# tx_no_transistor.net
KiCad netlist of a schematic drawn in EAGLE
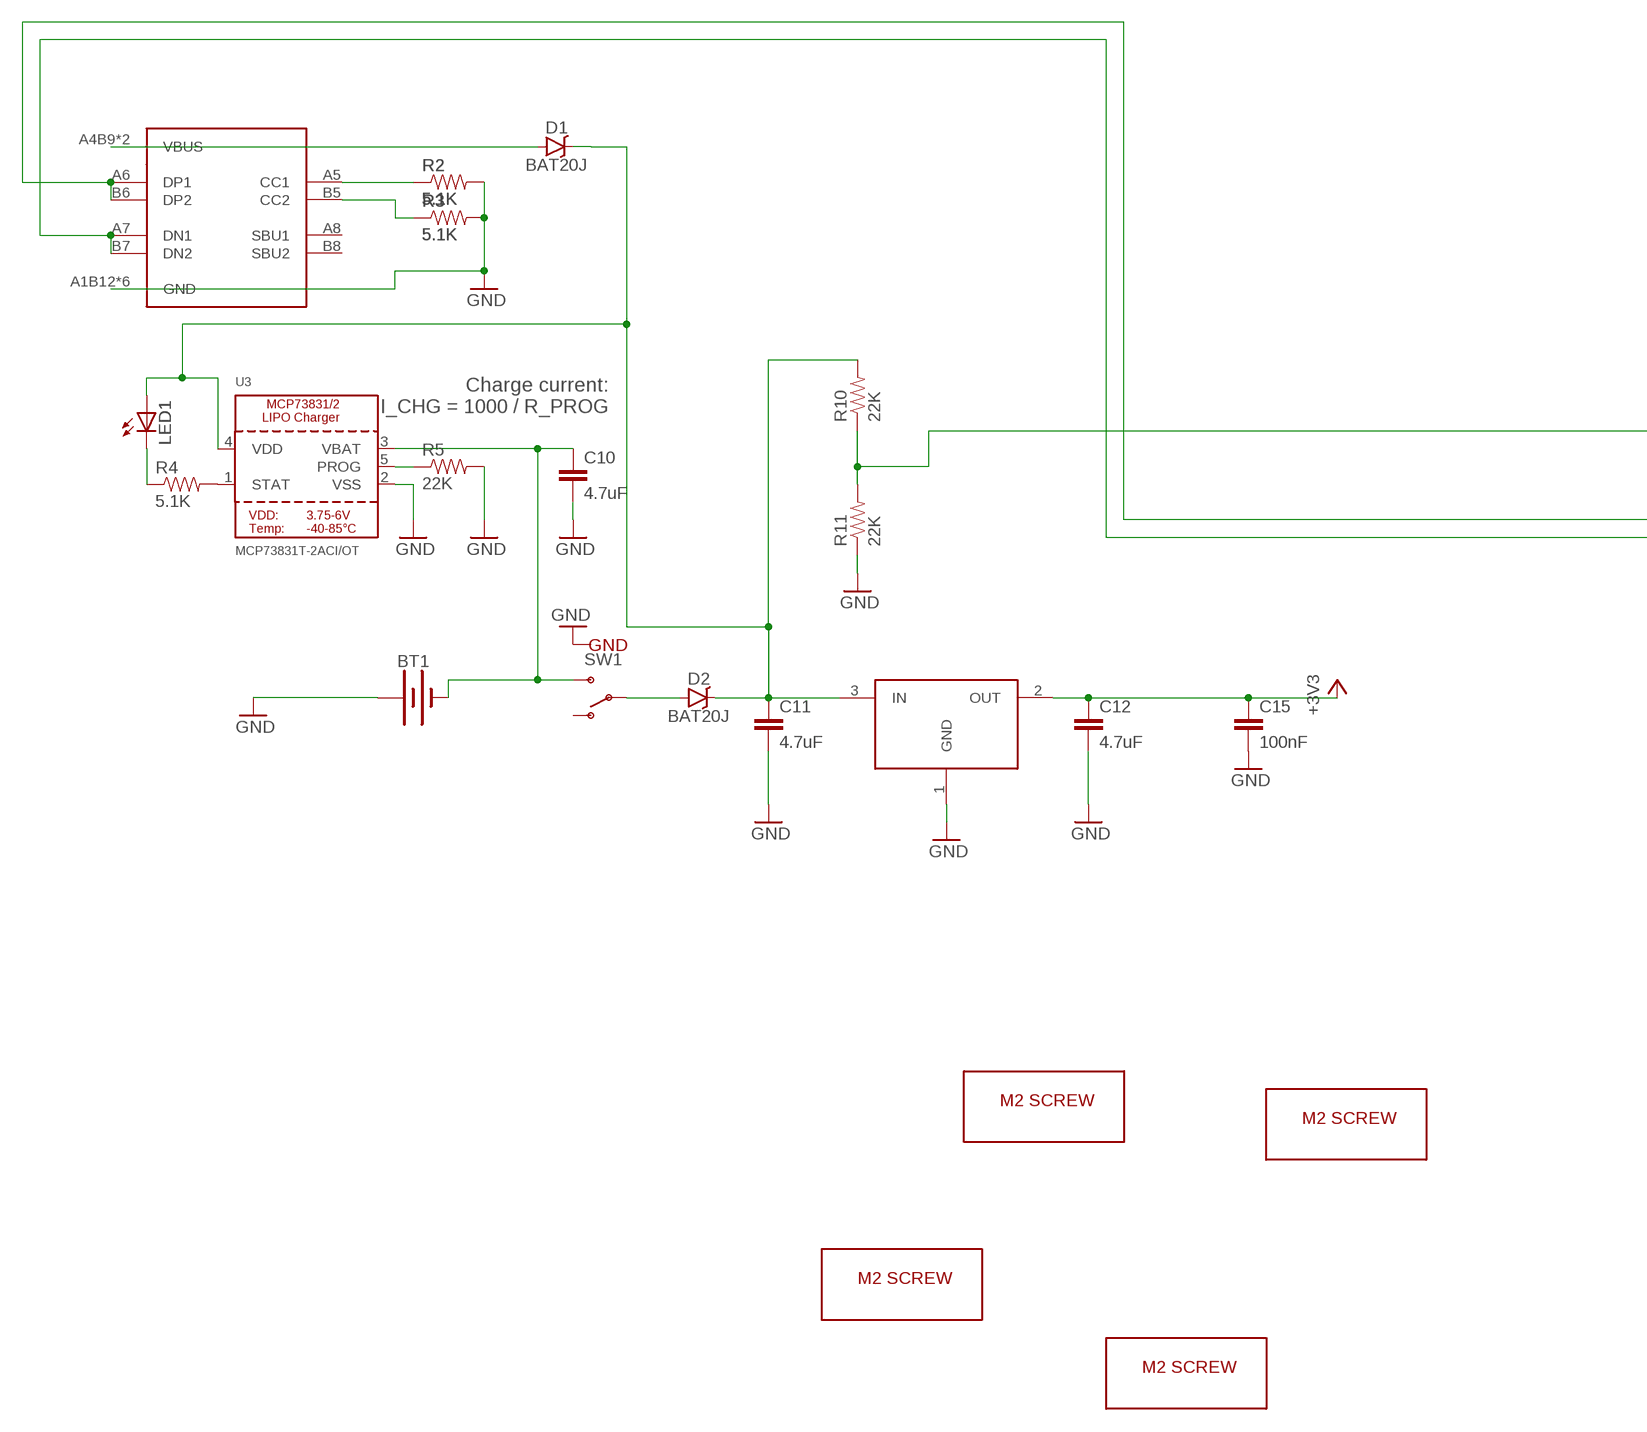
[diagram p0: schematic, sheet 1, part 1 of 2]
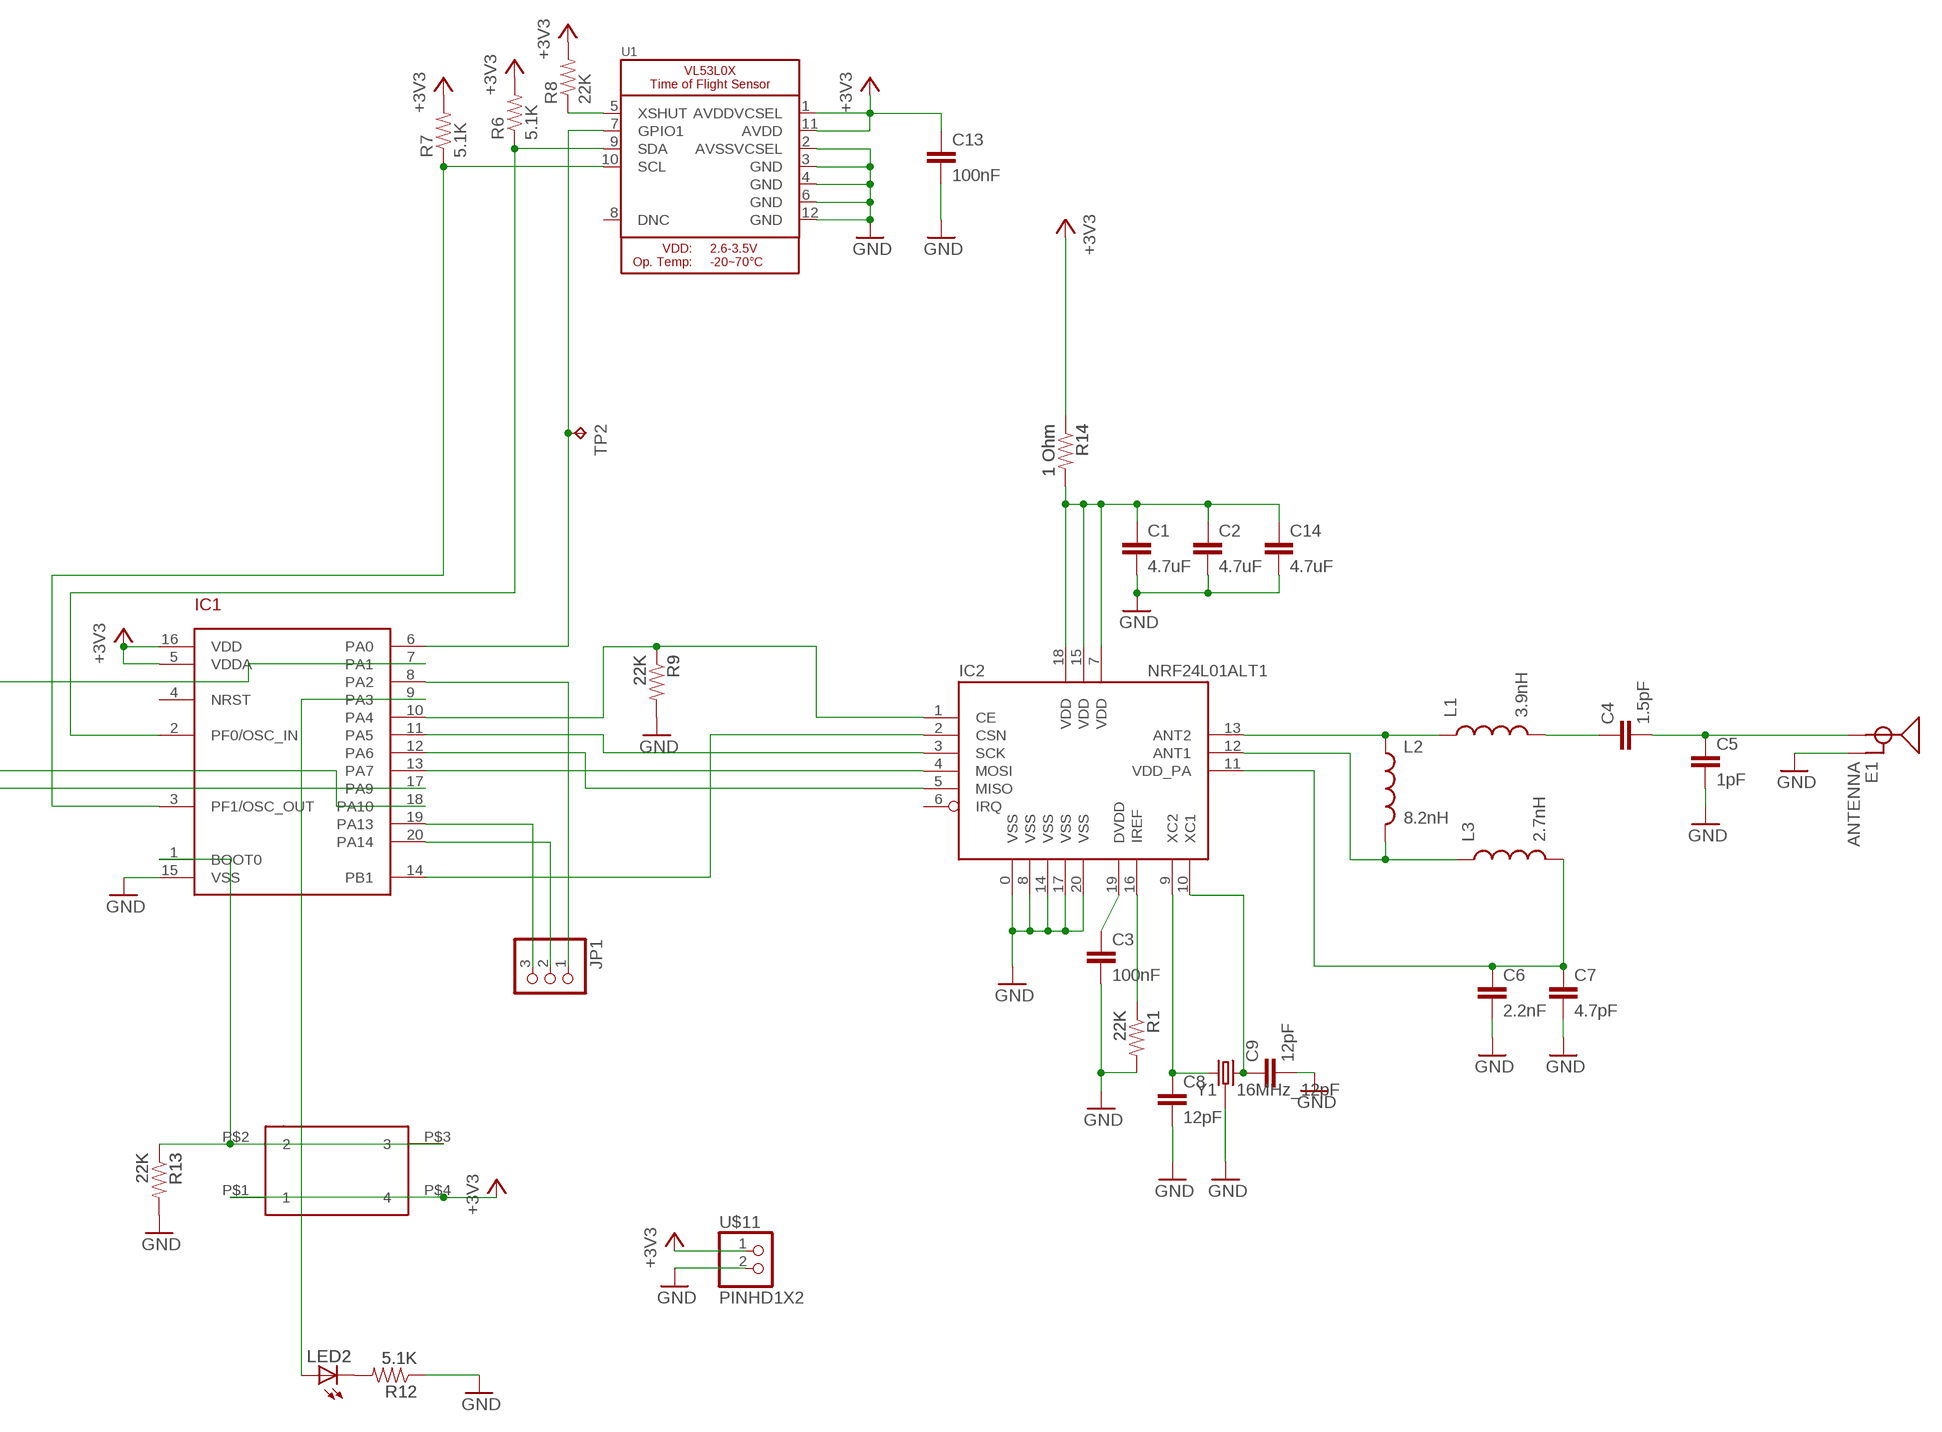
[diagram p1: schematic, sheet 1, part 2 of 2]

(export (version "E")
  (design (tool "Eeschema 10.0.6"))
  (components
    (comp (ref "BT1")
      (value "TX_SPARKFUN-BATTERIES_BATTERY-24.5MM_PTH")
      (footprint "eagle-import:TX_SPARKFUN-BATTERIES_BATTCON_24.5MM_PTH")
      (libsource (lib "eagle-import") (part "TX_SPARKFUN-BATTERIES_BATTERY-24.5MM_PTH"))
    )
    (comp (ref "C1")
      (value "4.7uF")
      (footprint "eagle-import:0805")
      (libsource (lib "eagle-import") (part "clock_CAP0805"))
    )
    (comp (ref "C2")
      (value "4.7uF")
      (footprint "eagle-import:0805")
      (libsource (lib "eagle-import") (part "clock_CAP0805"))
    )
    (comp (ref "C3")
      (value "100nF")
      (footprint "eagle-import:0805")
      (libsource (lib "eagle-import") (part "clock_CAP0805"))
    )
    (comp (ref "C4")
      (value "1.5pF")
      (footprint "eagle-import:0805")
      (libsource (lib "eagle-import") (part "clock_CAP0805"))
    )
    (comp (ref "C5")
      (value "1pF")
      (footprint "eagle-import:0805")
      (libsource (lib "eagle-import") (part "clock_CAP0805"))
    )
    (comp (ref "C6")
      (value "2.2nF")
      (footprint "eagle-import:0805")
      (libsource (lib "eagle-import") (part "clock_CAP0805"))
    )
    (comp (ref "C7")
      (value "4.7pF")
      (footprint "eagle-import:0805")
      (libsource (lib "eagle-import") (part "clock_CAP0805"))
    )
    (comp (ref "C8")
      (value "12pF")
      (footprint "eagle-import:0805")
      (libsource (lib "eagle-import") (part "clock_CAP0805"))
    )
    (comp (ref "C9")
      (value "12pF")
      (footprint "eagle-import:0805")
      (libsource (lib "eagle-import") (part "clock_CAP0805"))
    )
    (comp (ref "C10")
      (value "4.7uF")
      (footprint "eagle-import:0805")
      (libsource (lib "eagle-import") (part "CAP0805"))
    )
    (comp (ref "C11")
      (value "4.7uF")
      (footprint "eagle-import:0805")
      (libsource (lib "eagle-import") (part "clock_CAP0805"))
    )
    (comp (ref "C12")
      (value "4.7uF")
      (footprint "eagle-import:0805")
      (libsource (lib "eagle-import") (part "clock_CAP0805"))
    )
    (comp (ref "C13")
      (value "100nF")
      (footprint "eagle-import:0805")
      (libsource (lib "eagle-import") (part "clock_CAP0805"))
    )
    (comp (ref "C14")
      (value "4.7uF")
      (footprint "eagle-import:0805")
      (libsource (lib "eagle-import") (part "clock_CAP0805"))
    )
    (comp (ref "C15")
      (value "100nF")
      (footprint "eagle-import:0805")
      (libsource (lib "eagle-import") (part "clock_CAP0805"))
    )
    (comp (ref "D1")
      (value "BAT20J")
      (footprint "eagle-import:SOD-323")
      (libsource (lib "eagle-import") (part "DIODE-SCHOTTKY-BAT20J"))
    )
    (comp (ref "D2")
      (value "BAT20J")
      (footprint "eagle-import:SOD-323")
      (libsource (lib "eagle-import") (part "DIODE-SCHOTTKY-BAT20J"))
    )
    (comp (ref "E1")
      (value "ANTENNA")
      (footprint "eagle-import:TRACE_ANTENNA_2.4GHZ_25.7MM_TUNED")
      (libsource (lib "eagle-import") (part "ANTENNATRACE-TUNED"))
    )
    (comp (ref "IC1")
      (value "STM32F030F4")
      (footprint "eagle-import:TSSOP20")
      (libsource (lib "eagle-import") (part "STM32F030F4"))
    )
    (comp (ref "IC2")
      (value "NRF24L01ALT1")
      (footprint "eagle-import:QFN20_ALT1")
      (libsource (lib "eagle-import") (part "NRF24L01ALT1"))
    )
    (comp (ref "JP1")
      (value "PINHD-1X3CB")
      (footprint "eagle-import:1X03-CLEANBIG")
      (libsource (lib "eagle-import") (part "PINHD-1X3CB"))
    )
    (comp (ref "L1")
      (value "3.9nH")
      (footprint "eagle-import:0805")
      (libsource (lib "eagle-import") (part "INDUCTOR0805"))
    )
    (comp (ref "L2")
      (value "8.2nH")
      (footprint "eagle-import:0805")
      (libsource (lib "eagle-import") (part "INDUCTOR0805"))
    )
    (comp (ref "L3")
      (value "2.7nH")
      (footprint "eagle-import:0805")
      (libsource (lib "eagle-import") (part "INDUCTOR0805"))
    )
    (comp (ref "LED1")
      (value "LEDCHIP-LED0805")
      (footprint "eagle-import:CHIP-LED0805")
      (libsource (lib "eagle-import") (part "LEDCHIP-LED0805"))
    )
    (comp (ref "LED2")
      (value "LEDCHIP-LED0805")
      (footprint "eagle-import:CHIP-LED0805")
      (libsource (lib "eagle-import") (part "LEDCHIP-LED0805"))
    )
    (comp (ref "R1")
      (value "22K")
      (footprint "eagle-import:0805")
      (libsource (lib "eagle-import") (part "joyAnalog_RESISTOR0805-RES"))
    )
    (comp (ref "R2")
      (value "5.1K")
      (footprint "eagle-import:0805")
      (libsource (lib "eagle-import") (part "joyAnalog_RESISTOR0805-RES"))
    )
    (comp (ref "R3")
      (value "5.1K")
      (footprint "eagle-import:0805")
      (libsource (lib "eagle-import") (part "joyAnalog_RESISTOR0805-RES"))
    )
    (comp (ref "R4")
      (value "5.1K")
      (footprint "eagle-import:0805")
      (libsource (lib "eagle-import") (part "RESISTOR0805-RES"))
    )
    (comp (ref "R5")
      (value "22K")
      (footprint "eagle-import:0805")
      (libsource (lib "eagle-import") (part "RESISTOR0805-RES"))
    )
    (comp (ref "R6")
      (value "5.1K")
      (footprint "eagle-import:0805")
      (libsource (lib "eagle-import") (part "RESISTOR0805-RES"))
    )
    (comp (ref "R7")
      (value "5.1K")
      (footprint "eagle-import:0805")
      (libsource (lib "eagle-import") (part "RESISTOR0805-RES"))
    )
    (comp (ref "R8")
      (value "22K")
      (footprint "eagle-import:0805")
      (libsource (lib "eagle-import") (part "RESISTOR0805-RES"))
    )
    (comp (ref "R9")
      (value "22K")
      (footprint "eagle-import:0805")
      (libsource (lib "eagle-import") (part "joyAnalog_RESISTOR0805-RES"))
    )
    (comp (ref "R10")
      (value "22K")
      (footprint "eagle-import:0805")
      (libsource (lib "eagle-import") (part "RESISTOR0805-RES"))
    )
    (comp (ref "R11")
      (value "22K")
      (footprint "eagle-import:0805")
      (libsource (lib "eagle-import") (part "RESISTOR0805-RES"))
    )
    (comp (ref "R12")
      (value "5.1K")
      (footprint "eagle-import:0805")
      (libsource (lib "eagle-import") (part "joyAnalog_RESISTOR0805-RES"))
    )
    (comp (ref "R13")
      (value "22K")
      (footprint "eagle-import:0805")
      (libsource (lib "eagle-import") (part "joyAnalog_RESISTOR0805-RES"))
    )
    (comp (ref "R14")
      (value "1 Ohm")
      (footprint "eagle-import:0805")
      (libsource (lib "eagle-import") (part "joyAnalog_RESISTOR0805-RES"))
    )
    (comp (ref "SW1")
      (value "SWITCH-SPDTTDFGDFG")
      (footprint "eagle-import:SWITCH-SPST-SMD-A")
      (libsource (lib "eagle-import") (part "SWITCH-SPDTTDFGDFG"))
    )
    (comp (ref "SW2")
      (value "324_SW324_SWITCH_FOOT_HOLE")
      (footprint "eagle-import:342_SWICH_FOOT_HOLE")
      (libsource (lib "eagle-import") (part "324_SW324_SWITCH_FOOT_HOLE"))
    )
    (comp (ref "TP2")
      (value "TPTP10R")
      (footprint "eagle-import:TP10R")
      (libsource (lib "eagle-import") (part "TPTP10R"))
    )
    (comp (ref "U$1")
      (value "M2_SCREW_DEV")
      (footprint "eagle-import:M2_SCREW_FOOT")
      (libsource (lib "eagle-import") (part "M2_SCREW_DEV"))
    )
    (comp (ref "U$11")
      (value "PINHD1X2")
      (footprint "eagle-import:1X02")
      (libsource (lib "eagle-import") (part "PINHD1X2"))
    )
    (comp (ref "U$12")
      (value "M2_SCREW_DEV")
      (footprint "eagle-import:M2_SCREW_FOOT")
      (libsource (lib "eagle-import") (part "M2_SCREW_DEV"))
    )
    (comp (ref "U$13")
      (value "M2_SCREW_DEV")
      (footprint "eagle-import:M2_SCREW_FOOT")
      (libsource (lib "eagle-import") (part "M2_SCREW_DEV"))
    )
    (comp (ref "U$14")
      (value "M2_SCREW_DEV")
      (footprint "eagle-import:M2_SCREW_FOOT")
      (libsource (lib "eagle-import") (part "M2_SCREW_DEV"))
    )
    (comp (ref "U1")
      (value "VL53L0X")
      (footprint "eagle-import:LGA12_ST")
      (libsource (lib "eagle-import") (part "VL53L0X"))
    )
    (comp (ref "U2")
      (value "USBC_16P")
      (footprint "eagle-import:USBC_16P_FOOT")
      (libsource (lib "eagle-import") (part "USBC_16P"))
    )
    (comp (ref "U3")
      (value "MCP73831T-2ACI/OT")
      (footprint "eagle-import:SOT23-5")
      (libsource (lib "eagle-import") (part "MCP73831/2"))
    )
    (comp (ref "U4")
      (value "XC6206_DEV")
      (footprint "eagle-import:SOT23R_INFINEON")
      (libsource (lib "eagle-import") (part "XC6206_DEV"))
    )
    (comp (ref "Y1")
      (value "16MHz_12pF")
      (footprint "eagle-import:CRYSTAL-SMD-3.2X2.5MM")
      (libsource (lib "eagle-import") (part "CRYSTAL-26MHZSMD-3.2X2.5"))
    )
  )
  (nets
    (net (code "1") (name "+3V3") (class "Default")
      (node (ref "C12") (pin "1") (pinfunction "1_1") (pintype "passive"))
      (node (ref "C13") (pin "1") (pinfunction "1_1") (pintype "passive"))
      (node (ref "C15") (pin "1") (pinfunction "1_1") (pintype "passive"))
      (node (ref "IC1") (pin "16") (pinfunction "VDD_16") (pintype "bidirectional"))
      (node (ref "IC1") (pin "5") (pinfunction "VDDA_5") (pintype "bidirectional"))
      (node (ref "R14") (pin "1") (pinfunction "1_1") (pintype "passive"))
      (node (ref "R6") (pin "2") (pinfunction "2_2") (pintype "passive"))
      (node (ref "R7") (pin "2") (pinfunction "2_2") (pintype "passive"))
      (node (ref "R8") (pin "2") (pinfunction "2_2") (pintype "passive"))
      (node (ref "SW2") (pin "P$1") (pinfunction "1_P$1") (pintype "bidirectional"))
      (node (ref "SW2") (pin "P$4") (pinfunction "4_P$4") (pintype "bidirectional"))
      (node (ref "U$11") (pin "1") (pinfunction "1_1") (pintype "passive"))
      (node (ref "U1") (pin "1") (pinfunction "AVDDVCSEL_1") (pintype "power_in"))
      (node (ref "U1") (pin "11") (pinfunction "AVDD_11") (pintype "power_in"))
      (node (ref "U4") (pin "2") (pinfunction "OUT_2") (pintype "bidirectional"))
    )
    (net (code "2") (name "GND") (class "Default")
      (node (ref "BT1") (pin "2") (pinfunction "+_2") (pintype "power_in"))
      (node (ref "C1") (pin "2") (pinfunction "2_2") (pintype "passive"))
      (node (ref "C10") (pin "2") (pinfunction "2_2") (pintype "passive"))
      (node (ref "C11") (pin "2") (pinfunction "2_2") (pintype "passive"))
      (node (ref "C12") (pin "2") (pinfunction "2_2") (pintype "passive"))
      (node (ref "C13") (pin "2") (pinfunction "2_2") (pintype "passive"))
      (node (ref "C14") (pin "2") (pinfunction "2_2") (pintype "passive"))
      (node (ref "C15") (pin "2") (pinfunction "2_2") (pintype "passive"))
      (node (ref "C2") (pin "2") (pinfunction "2_2") (pintype "passive"))
      (node (ref "C3") (pin "2") (pinfunction "2_2") (pintype "passive"))
      (node (ref "C5") (pin "2") (pinfunction "2_2") (pintype "passive"))
      (node (ref "C6") (pin "2") (pinfunction "2_2") (pintype "passive"))
      (node (ref "C7") (pin "2") (pinfunction "2_2") (pintype "passive"))
      (node (ref "C8") (pin "2") (pinfunction "2_2") (pintype "passive"))
      (node (ref "C9") (pin "2") (pinfunction "2_2") (pintype "passive"))
      (node (ref "E1") (pin "GND") (pinfunction "GND_GND") (pintype "bidirectional"))
      (node (ref "E1") (pin "GND2") (pinfunction "GND_GND2") (pintype "bidirectional"))
      (node (ref "IC1") (pin "15") (pinfunction "VSS_15") (pintype "bidirectional"))
      (node (ref "IC2") (pin "0") (pinfunction "VSS_0") (pintype "power_in"))
      (node (ref "IC2") (pin "14") (pinfunction "VSS_14") (pintype "power_in"))
      (node (ref "IC2") (pin "17") (pinfunction "VSS_17") (pintype "power_in"))
      (node (ref "IC2") (pin "20") (pinfunction "VSS_20") (pintype "power_in"))
      (node (ref "IC2") (pin "8") (pinfunction "VSS_8") (pintype "power_in"))
      (node (ref "R1") (pin "2") (pinfunction "2_2") (pintype "passive"))
      (node (ref "R11") (pin "1") (pinfunction "1_1") (pintype "passive"))
      (node (ref "R12") (pin "1") (pinfunction "1_1") (pintype "passive"))
      (node (ref "R13") (pin "2") (pinfunction "2_2") (pintype "passive"))
      (node (ref "R2") (pin "2") (pinfunction "2_2") (pintype "passive"))
      (node (ref "R3") (pin "2") (pinfunction "2_2") (pintype "passive"))
      (node (ref "R5") (pin "2") (pinfunction "2_2") (pintype "passive"))
      (node (ref "R9") (pin "2") (pinfunction "2_2") (pintype "passive"))
      (node (ref "SW1") (pin "G1") (pinfunction "GND_G1") (pintype "passive"))
      (node (ref "SW1") (pin "G2") (pinfunction "GND_G2") (pintype "passive"))
      (node (ref "SW1") (pin "G3") (pinfunction "GND_G3") (pintype "passive"))
      (node (ref "SW1") (pin "G4") (pinfunction "GND_G4") (pintype "passive"))
      (node (ref "U$11") (pin "2") (pinfunction "2_2") (pintype "passive"))
      (node (ref "U1") (pin "12") (pinfunction "GND_12") (pintype "power_in"))
      (node (ref "U1") (pin "2") (pinfunction "AVSSVCSEL_2") (pintype "power_in"))
      (node (ref "U1") (pin "3") (pinfunction "GND_3") (pintype "power_in"))
      (node (ref "U1") (pin "4") (pinfunction "GND_4") (pintype "power_in"))
      (node (ref "U1") (pin "6") (pinfunction "GND_6") (pintype "power_in"))
      (node (ref "U2") (pin "A1B12") (pinfunction "GND_A1B12") (pintype "bidirectional"))
      (node (ref "U2") (pin "B11A12") (pinfunction "GND_B11A12") (pintype "bidirectional"))
      (node (ref "U2") (pin "P$13") (pinfunction "GND_P$13") (pintype "bidirectional"))
      (node (ref "U2") (pin "P$14") (pinfunction "GND_P$14") (pintype "bidirectional"))
      (node (ref "U2") (pin "P$15") (pinfunction "GND_P$15") (pintype "bidirectional"))
      (node (ref "U2") (pin "P$16") (pinfunction "GND_P$16") (pintype "bidirectional"))
      (node (ref "U3") (pin "2") (pinfunction "VSS_2") (pintype "power_in"))
      (node (ref "U4") (pin "1") (pinfunction "GND_1") (pintype "bidirectional"))
      (node (ref "Y1") (pin "2") (pinfunction "3_2") (pintype "passive"))
      (node (ref "Y1") (pin "4") (pinfunction "3_4") (pintype "passive"))
    )
    (net (code "3") (name "Net-(BT1--)") (class "Default")
      (node (ref "BT1") (pin "1") (pinfunction "-_1") (pintype "power_in"))
      (node (ref "C10") (pin "1") (pinfunction "1_1") (pintype "passive"))
      (node (ref "SW1") (pin "3") (pinfunction "S_3") (pintype "passive"))
      (node (ref "U3") (pin "3") (pinfunction "VBAT_3") (pintype "power_in"))
    )
    (net (code "4") (name "Net-(C1-Pad1)") (class "Default")
      (node (ref "C1") (pin "1") (pinfunction "1_1") (pintype "passive"))
      (node (ref "C14") (pin "1") (pinfunction "1_1") (pintype "passive"))
      (node (ref "C2") (pin "1") (pinfunction "1_1") (pintype "passive"))
      (node (ref "IC2") (pin "15") (pinfunction "VDD_15") (pintype "power_in"))
      (node (ref "IC2") (pin "18") (pinfunction "VDD_18") (pintype "power_in"))
      (node (ref "IC2") (pin "7") (pinfunction "VDD_7") (pintype "power_in"))
      (node (ref "R14") (pin "2") (pinfunction "2_2") (pintype "passive"))
    )
    (net (code "5") (name "Net-(C4-Pad1)") (class "Default")
      (node (ref "C4") (pin "1") (pinfunction "1_1") (pintype "passive"))
      (node (ref "L1") (pin "2") (pinfunction "2_2") (pintype "passive"))
    )
    (net (code "6") (name "Net-(D1-PadA)") (class "Default")
      (node (ref "D1") (pin "A") (pinfunction "A_A") (pintype "passive"))
      (node (ref "U2") (pin "A4B9") (pinfunction "VBUS_A4B9") (pintype "bidirectional"))
      (node (ref "U2") (pin "B4A9") (pinfunction "VBUS_B4A9") (pintype "bidirectional"))
    )
    (net (code "7") (name "Net-(E1-SIGNAL)") (class "Default")
      (node (ref "C4") (pin "2") (pinfunction "2_2") (pintype "passive"))
      (node (ref "C5") (pin "1") (pinfunction "1_1") (pintype "passive"))
      (node (ref "E1") (pin "ANT") (pinfunction "SIGNAL_ANT") (pintype "bidirectional"))
    )
    (net (code "8") (name "Net-(IC1-BOOT0)") (class "Default")
      (node (ref "IC1") (pin "1") (pinfunction "BOOT0_1") (pintype "bidirectional"))
      (node (ref "R13") (pin "1") (pinfunction "1_1") (pintype "passive"))
      (node (ref "SW2") (pin "P$2") (pinfunction "2_P$2") (pintype "bidirectional"))
      (node (ref "SW2") (pin "P$3") (pinfunction "3_P$3") (pintype "bidirectional"))
    )
    (net (code "9") (name "Net-(IC1-PA0)") (class "Default")
      (node (ref "IC1") (pin "6") (pinfunction "PA0_6") (pintype "bidirectional"))
      (node (ref "TP2") (pin "TP") (pinfunction "TP_TP") (pintype "input"))
      (node (ref "U1") (pin "7") (pinfunction "GPIO1_7") (pintype "output"))
    )
    (net (code "10") (name "Net-(IC1-PA1)") (class "Default")
      (node (ref "IC1") (pin "7") (pinfunction "PA1_7") (pintype "bidirectional"))
      (node (ref "R10") (pin "1") (pinfunction "1_1") (pintype "passive"))
      (node (ref "R11") (pin "2") (pinfunction "2_2") (pintype "passive"))
    )
    (net (code "11") (name "Net-(IC1-PA2)") (class "Default")
      (node (ref "IC1") (pin "8") (pinfunction "PA2_8") (pintype "bidirectional"))
      (node (ref "JP1") (pin "1") (pinfunction "1_1") (pintype "passive"))
    )
    (net (code "12") (name "Net-(IC1-PA3)") (class "Default")
      (node (ref "IC1") (pin "9") (pinfunction "PA3_9") (pintype "bidirectional"))
      (node (ref "LED2") (pin "A") (pinfunction "A_A") (pintype "passive"))
    )
    (net (code "13") (name "Net-(IC1-PA4)") (class "Default")
      (node (ref "IC1") (pin "10") (pinfunction "PA4_10") (pintype "bidirectional"))
      (node (ref "IC2") (pin "1") (pinfunction "CE_1") (pintype "input"))
      (node (ref "R9") (pin "1") (pinfunction "1_1") (pintype "passive"))
    )
    (net (code "14") (name "Net-(IC1-PA5)") (class "Default")
      (node (ref "IC1") (pin "11") (pinfunction "PA5_11") (pintype "bidirectional"))
      (node (ref "IC2") (pin "3") (pinfunction "SCK_3") (pintype "input"))
    )
    (net (code "15") (name "Net-(IC1-PA6)") (class "Default")
      (node (ref "IC1") (pin "12") (pinfunction "PA6_12") (pintype "bidirectional"))
      (node (ref "IC2") (pin "5") (pinfunction "MISO_5") (pintype "output"))
    )
    (net (code "16") (name "Net-(IC1-PA7)") (class "Default")
      (node (ref "IC1") (pin "13") (pinfunction "PA7_13") (pintype "bidirectional"))
      (node (ref "IC2") (pin "4") (pinfunction "MOSI_4") (pintype "input"))
    )
    (net (code "17") (name "Net-(IC1-PA9)") (class "Default")
      (node (ref "IC1") (pin "17") (pinfunction "PA9_17") (pintype "bidirectional"))
      (node (ref "U2") (pin "A7") (pinfunction "DN1_A7") (pintype "bidirectional"))
      (node (ref "U2") (pin "B7") (pinfunction "DN2_B7") (pintype "bidirectional"))
    )
    (net (code "18") (name "Net-(IC1-PA10)") (class "Default")
      (node (ref "IC1") (pin "18") (pinfunction "PA10_18") (pintype "bidirectional"))
      (node (ref "U2") (pin "A6") (pinfunction "DP1_A6") (pintype "bidirectional"))
      (node (ref "U2") (pin "B6") (pinfunction "DP2_B6") (pintype "bidirectional"))
    )
    (net (code "19") (name "Net-(IC1-PA13)") (class "Default")
      (node (ref "IC1") (pin "19") (pinfunction "PA13_19") (pintype "bidirectional"))
      (node (ref "JP1") (pin "3") (pinfunction "3_3") (pintype "passive"))
    )
    (net (code "20") (name "Net-(IC1-PA14)") (class "Default")
      (node (ref "IC1") (pin "20") (pinfunction "PA14_20") (pintype "bidirectional"))
      (node (ref "JP1") (pin "2") (pinfunction "2_2") (pintype "passive"))
    )
    (net (code "21") (name "Net-(IC1-PB1)") (class "Default")
      (node (ref "IC1") (pin "14") (pinfunction "PB1_14") (pintype "bidirectional"))
      (node (ref "IC2") (pin "2") (pinfunction "CSN_2") (pintype "input"))
    )
    (net (code "22") (name "Net-(IC1-PF0{slash}OSC_IN)") (class "Default")
      (node (ref "IC1") (pin "2") (pinfunction "PF0/OSC_IN_2") (pintype "bidirectional"))
      (node (ref "R6") (pin "1") (pinfunction "1_1") (pintype "passive"))
      (node (ref "U1") (pin "9") (pinfunction "SDA_9") (pintype "open_collector"))
    )
    (net (code "23") (name "Net-(IC1-PF1{slash}OSC_OUT)") (class "Default")
      (node (ref "IC1") (pin "3") (pinfunction "PF1/OSC_OUT_3") (pintype "bidirectional"))
      (node (ref "R7") (pin "1") (pinfunction "1_1") (pintype "passive"))
      (node (ref "U1") (pin "10") (pinfunction "SCL_10") (pintype "open_collector"))
    )
    (net (code "24") (name "Net-(IC2-ANT1)") (class "Default")
      (node (ref "IC2") (pin "12") (pinfunction "ANT1_12") (pintype "output"))
      (node (ref "L2") (pin "2") (pinfunction "2_2") (pintype "passive"))
      (node (ref "L3") (pin "1") (pinfunction "1_1") (pintype "passive"))
    )
    (net (code "25") (name "Net-(IC2-ANT2)") (class "Default")
      (node (ref "IC2") (pin "13") (pinfunction "ANT2_13") (pintype "output"))
      (node (ref "L1") (pin "1") (pinfunction "1_1") (pintype "passive"))
      (node (ref "L2") (pin "1") (pinfunction "1_1") (pintype "passive"))
    )
    (net (code "26") (name "Net-(IC2-DVDD)") (class "Default")
      (node (ref "C3") (pin "1") (pinfunction "1_1") (pintype "passive"))
      (node (ref "IC2") (pin "19") (pinfunction "DVDD_19") (pintype "power_in"))
    )
    (net (code "27") (name "Net-(IC2-IREF)") (class "Default")
      (node (ref "IC2") (pin "16") (pinfunction "IREF_16") (pintype "input"))
      (node (ref "R1") (pin "1") (pinfunction "1_1") (pintype "passive"))
    )
    (net (code "28") (name "Net-(IC2-VDD_PA)") (class "Default")
      (node (ref "C6") (pin "1") (pinfunction "1_1") (pintype "passive"))
      (node (ref "C7") (pin "1") (pinfunction "1_1") (pintype "passive"))
      (node (ref "IC2") (pin "11") (pinfunction "VDD_PA_11") (pintype "power_in"))
      (node (ref "L3") (pin "2") (pinfunction "2_2") (pintype "passive"))
    )
    (net (code "29") (name "Net-(IC2-XC1)") (class "Default")
      (node (ref "C9") (pin "1") (pinfunction "1_1") (pintype "passive"))
      (node (ref "IC2") (pin "10") (pinfunction "XC1_10") (pintype "input"))
      (node (ref "Y1") (pin "3") (pinfunction "2_3") (pintype "passive"))
    )
    (net (code "30") (name "Net-(IC2-XC2)") (class "Default")
      (node (ref "C8") (pin "1") (pinfunction "1_1") (pintype "passive"))
      (node (ref "IC2") (pin "9") (pinfunction "XC2_9") (pintype "input"))
      (node (ref "Y1") (pin "1") (pinfunction "1_1") (pintype "passive"))
    )
    (net (code "31") (name "Net-(LED1-PadC)") (class "Default")
      (node (ref "LED1") (pin "C") (pinfunction "C_C") (pintype "passive"))
      (node (ref "R4") (pin "1") (pinfunction "1_1") (pintype "passive"))
    )
    (net (code "32") (name "Net-(LED2-PadC)") (class "Default")
      (node (ref "LED2") (pin "C") (pinfunction "C_C") (pintype "passive"))
      (node (ref "R12") (pin "2") (pinfunction "2_2") (pintype "passive"))
    )
    (net (code "33") (name "Net-(SW1-P)") (class "Default")
      (node (ref "D2") (pin "A") (pinfunction "A_A") (pintype "passive"))
      (node (ref "SW1") (pin "2") (pinfunction "P_2") (pintype "passive"))
    )
    (net (code "34") (name "Net-(U1-XSHUT)") (class "Default")
      (node (ref "R8") (pin "1") (pinfunction "1_1") (pintype "passive"))
      (node (ref "U1") (pin "5") (pinfunction "XSHUT_5") (pintype "input"))
    )
    (net (code "35") (name "Net-(U2-CC1)") (class "Default")
      (node (ref "R2") (pin "1") (pinfunction "1_1") (pintype "passive"))
      (node (ref "U2") (pin "A5") (pinfunction "CC1_A5") (pintype "bidirectional"))
    )
    (net (code "36") (name "Net-(U2-CC2)") (class "Default")
      (node (ref "R3") (pin "1") (pinfunction "1_1") (pintype "passive"))
      (node (ref "U2") (pin "B5") (pinfunction "CC2_B5") (pintype "bidirectional"))
    )
    (net (code "37") (name "Net-(U3-PROG)") (class "Default")
      (node (ref "R5") (pin "1") (pinfunction "1_1") (pintype "passive"))
      (node (ref "U3") (pin "5") (pinfunction "PROG_5") (pintype "input"))
    )
    (net (code "38") (name "Net-(U3-STAT)") (class "Default")
      (node (ref "R4") (pin "2") (pinfunction "2_2") (pintype "passive"))
      (node (ref "U3") (pin "1") (pinfunction "STAT_1") (pintype "output"))
    )
    (net (code "39") (name "Net-(U3-VDD)") (class "Default")
      (node (ref "C11") (pin "1") (pinfunction "1_1") (pintype "passive"))
      (node (ref "D1") (pin "C") (pinfunction "C_C") (pintype "passive"))
      (node (ref "D2") (pin "C") (pinfunction "C_C") (pintype "passive"))
      (node (ref "LED1") (pin "A") (pinfunction "A_A") (pintype "passive"))
      (node (ref "R10") (pin "2") (pinfunction "2_2") (pintype "passive"))
      (node (ref "U3") (pin "4") (pinfunction "VDD_4") (pintype "power_in"))
      (node (ref "U4") (pin "3") (pinfunction "IN_3") (pintype "bidirectional"))
    )
    (net (code "40") (name "unconnected-(IC1-NRST-Pad4)") (class "Default")
      (node (ref "IC1") (pin "4") (pinfunction "NRST_4") (pintype "bidirectional"))
    )
    (net (code "41") (name "unconnected-(IC2-IRQ-Pad6)") (class "Default")
      (node (ref "IC2") (pin "6") (pinfunction "IRQ_6") (pintype "output"))
    )
    (net (code "42") (name "unconnected-(SW1-O-Pad1)") (class "Default")
      (node (ref "SW1") (pin "1") (pinfunction "O_1") (pintype "passive"))
    )
    (net (code "43") (name "unconnected-(U1-DNC-Pad8)") (class "Default")
      (node (ref "U1") (pin "8") (pinfunction "DNC_8") (pintype "no_connect"))
    )
    (net (code "44") (name "unconnected-(U2-SBU1-PadA8)") (class "Default")
      (node (ref "U2") (pin "A8") (pinfunction "SBU1_A8") (pintype "bidirectional"))
    )
    (net (code "45") (name "unconnected-(U2-SBU2-PadB8)") (class "Default")
      (node (ref "U2") (pin "B8") (pinfunction "SBU2_B8") (pintype "bidirectional"))
    )
  )
)
